# Mach_cum_LED.net
KiCad netlist of a schematic drawn in Altium Designer
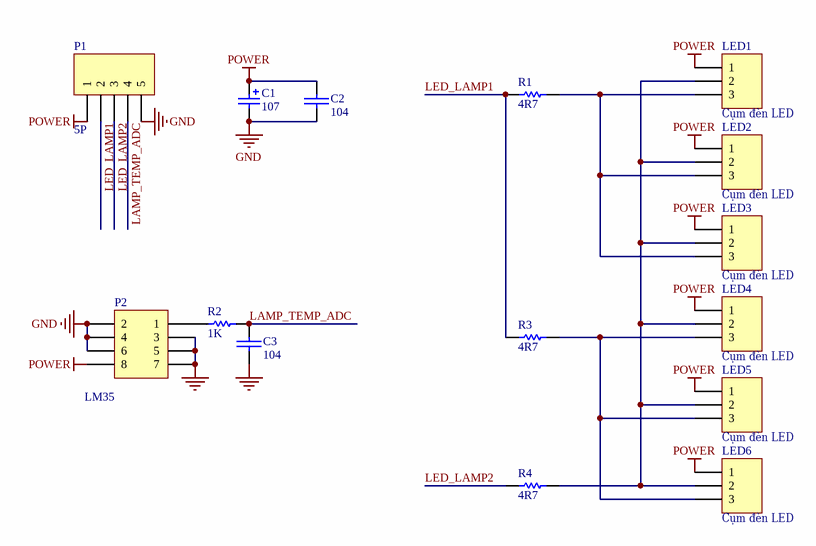
[diagram p0: Mach cum LED.SchDoc]

(export (version "E")
  (design (tool "Eeschema 10.0.6"))
  (components
    (comp (ref "C1")
      (value "107")
      (footprint "SMC_D/WA")
      (description "Polarized Capacitor (Radial)")
      (fields (field (name "Comment") "Tụ hóa chân dán107") (field (name "PUBLISHER") "*"))
      (libsource (lib "DnsSchLib") (part "Cap Pol1"))
    )
    (comp (ref "C2")
      (value "104")
      (footprint "0805C")
      (fields (field (name "Comment") "Tụ điện dán 0805104"))
      (libsource (lib "DnsSchLib") (part "CAP"))
    )
    (comp (ref "C3")
      (value "104")
      (footprint "0805C")
      (fields (field (name "Comment") "Tụ điện dán 0805104"))
      (libsource (lib "DnsSchLib") (part "CAP"))
    )
    (comp (ref "LED1")
      (value "Cụm đèn LED")
      (footprint "LED_5730")
      (description "Header, 3-Pin")
      (fields (field (name "PUBLISHER") "Altium Limited"))
      (libsource (lib "Miscellaneous Connectors") (part "Header 3"))
    )
    (comp (ref "LED2")
      (value "Cụm đèn LED")
      (footprint "LED_5730")
      (description "Header, 3-Pin")
      (fields (field (name "PUBLISHER") "Altium Limited"))
      (libsource (lib "Miscellaneous Connectors") (part "Header 3"))
    )
    (comp (ref "LED3")
      (value "Cụm đèn LED")
      (footprint "LED_5730")
      (description "Header, 3-Pin")
      (fields (field (name "PUBLISHER") "Altium Limited"))
      (libsource (lib "Miscellaneous Connectors") (part "Header 3"))
    )
    (comp (ref "LED4")
      (value "Cụm đèn LED")
      (footprint "LED_5730")
      (description "Header, 3-Pin")
      (fields (field (name "PUBLISHER") "Altium Limited"))
      (libsource (lib "Miscellaneous Connectors") (part "Header 3"))
    )
    (comp (ref "LED5")
      (value "Cụm đèn LED")
      (footprint "LED_5730")
      (description "Header, 3-Pin")
      (fields (field (name "PUBLISHER") "Altium Limited"))
      (libsource (lib "Miscellaneous Connectors") (part "Header 3"))
    )
    (comp (ref "LED6")
      (value "Cụm đèn LED")
      (footprint "LED_5730")
      (description "Header, 3-Pin")
      (fields (field (name "PUBLISHER") "Altium Limited"))
      (libsource (lib "Miscellaneous Connectors") (part "Header 3"))
    )
    (comp (ref "P1")
      (value "5P")
      (footprint "HDR1X5H")
      (description "Header, 5-Pin, Right Angle")
      (fields
        (field (name "Comment") "Jump đực chân thẳng, 2.54mm 5P")
        (field (name "PUBLISHER") "Altium Limited")
      )
      (libsource (lib "Miscellaneous Connectors") (part "Header 5H"))
    )
    (comp (ref "P2")
      (value "LM35")
      (footprint "so-8")
      (description "Header, 4-Pin, Dual row")
      (fields
        (field (name "Comment") "IC đo nhiệt độ, chân dán 8P LM35")
        (field (name "PUBLISHER") "Altium Limited")
      )
      (libsource (lib "Miscellaneous Connectors") (part "Header 4X2"))
    )
    (comp (ref "R1")
      (value "4R7")
      (footprint "2512")
      (description "Semiconductor Resistor")
      (fields (field (name "Comment") "Điện trở dán 25124R7") (field (name "PUBLISHER") "*"))
      (libsource (lib "DnsSchLib") (part "Res Semi"))
    )
    (comp (ref "R2")
      (value "1K")
      (footprint "0805DD")
      (description "Semiconductor Resistor")
      (fields (field (name "Comment") "Điện trở dán 08051K") (field (name "PUBLISHER") "*"))
      (libsource (lib "DnsSchLib") (part "Res Semi"))
    )
    (comp (ref "R3")
      (value "4R7")
      (footprint "2512")
      (description "Semiconductor Resistor")
      (fields (field (name "Comment") "Điện trở dán 25124R7") (field (name "PUBLISHER") "*"))
      (libsource (lib "DnsSchLib") (part "Res Semi"))
    )
    (comp (ref "R4")
      (value "4R7")
      (footprint "2512")
      (description "Semiconductor Resistor")
      (fields (field (name "Comment") "Điện trở dán 25124R7") (field (name "PUBLISHER") "*"))
      (libsource (lib "DnsSchLib") (part "Res Semi"))
    )
  )
  (nets
    (net (code "1") (name "/LAMP_TEMP_ADC") (class "Default")
      (node (ref "C3") (pin "1") (pinfunction "1_1") (pintype "passive"))
      (node (ref "P1") (pin "4") (pinfunction "4_4") (pintype "passive"))
      (node (ref "R2") (pin "2") (pinfunction "2_2") (pintype "passive"))
    )
    (net (code "2") (name "/LED_LAMP1") (class "Default")
      (node (ref "P1") (pin "2") (pinfunction "2_2") (pintype "passive"))
      (node (ref "R1") (pin "1") (pinfunction "1_1") (pintype "passive"))
      (node (ref "R3") (pin "1") (pinfunction "1_1") (pintype "passive"))
    )
    (net (code "3") (name "/LED_LAMP2") (class "Default")
      (node (ref "P1") (pin "3") (pinfunction "3_3") (pintype "passive"))
      (node (ref "R4") (pin "2") (pinfunction "2_2") (pintype "passive"))
    )
    (net (code "4") (name "GND") (class "Default")
      (node (ref "C1") (pin "2") (pinfunction "2_2") (pintype "passive"))
      (node (ref "C2") (pin "2") (pinfunction "2_2") (pintype "passive"))
      (node (ref "C3") (pin "2") (pinfunction "2_2") (pintype "passive"))
      (node (ref "P1") (pin "5") (pinfunction "5_5") (pintype "passive"))
      (node (ref "P2") (pin "2") (pinfunction "2_2") (pintype "passive"))
      (node (ref "P2") (pin "3") (pinfunction "3_3") (pintype "passive"))
      (node (ref "P2") (pin "4") (pinfunction "4_4") (pintype "passive"))
      (node (ref "P2") (pin "5") (pinfunction "5_5") (pintype "passive"))
      (node (ref "P2") (pin "6") (pinfunction "6_6") (pintype "passive"))
      (node (ref "P2") (pin "7") (pinfunction "7_7") (pintype "passive"))
    )
    (net (code "5") (name "Net-(LED1-Pad2)") (class "Default")
      (node (ref "LED1") (pin "2") (pinfunction "2_2") (pintype "passive"))
      (node (ref "LED2") (pin "2") (pinfunction "2_2") (pintype "passive"))
      (node (ref "LED3") (pin "2") (pinfunction "2_2") (pintype "passive"))
      (node (ref "LED4") (pin "2") (pinfunction "2_2") (pintype "passive"))
      (node (ref "LED5") (pin "2") (pinfunction "2_2") (pintype "passive"))
      (node (ref "LED6") (pin "2") (pinfunction "2_2") (pintype "passive"))
      (node (ref "R4") (pin "1") (pinfunction "1_1") (pintype "passive"))
    )
    (net (code "6") (name "Net-(LED1-Pad3)") (class "Default")
      (node (ref "LED1") (pin "3") (pinfunction "3_3") (pintype "passive"))
      (node (ref "LED2") (pin "3") (pinfunction "3_3") (pintype "passive"))
      (node (ref "LED3") (pin "3") (pinfunction "3_3") (pintype "passive"))
      (node (ref "R1") (pin "2") (pinfunction "2_2") (pintype "passive"))
    )
    (net (code "7") (name "Net-(LED4-Pad3)") (class "Default")
      (node (ref "LED4") (pin "3") (pinfunction "3_3") (pintype "passive"))
      (node (ref "LED5") (pin "3") (pinfunction "3_3") (pintype "passive"))
      (node (ref "LED6") (pin "3") (pinfunction "3_3") (pintype "passive"))
      (node (ref "R3") (pin "2") (pinfunction "2_2") (pintype "passive"))
    )
    (net (code "8") (name "Net-(P2-Pad1)") (class "Default")
      (node (ref "P2") (pin "1") (pinfunction "1_1") (pintype "passive"))
      (node (ref "R2") (pin "1") (pinfunction "1_1") (pintype "passive"))
    )
    (net (code "9") (name "POWER") (class "Default")
      (node (ref "C1") (pin "1") (pinfunction "1_1") (pintype "passive"))
      (node (ref "C2") (pin "1") (pinfunction "1_1") (pintype "passive"))
      (node (ref "LED1") (pin "1") (pinfunction "1_1") (pintype "passive"))
      (node (ref "LED2") (pin "1") (pinfunction "1_1") (pintype "passive"))
      (node (ref "LED3") (pin "1") (pinfunction "1_1") (pintype "passive"))
      (node (ref "LED4") (pin "1") (pinfunction "1_1") (pintype "passive"))
      (node (ref "LED5") (pin "1") (pinfunction "1_1") (pintype "passive"))
      (node (ref "LED6") (pin "1") (pinfunction "1_1") (pintype "passive"))
      (node (ref "P1") (pin "1") (pinfunction "1_1") (pintype "passive"))
      (node (ref "P2") (pin "8") (pinfunction "8_8") (pintype "passive"))
    )
  )
)
